# connect_4_v4.net
KiCad netlist of a schematic drawn in EasyEDA
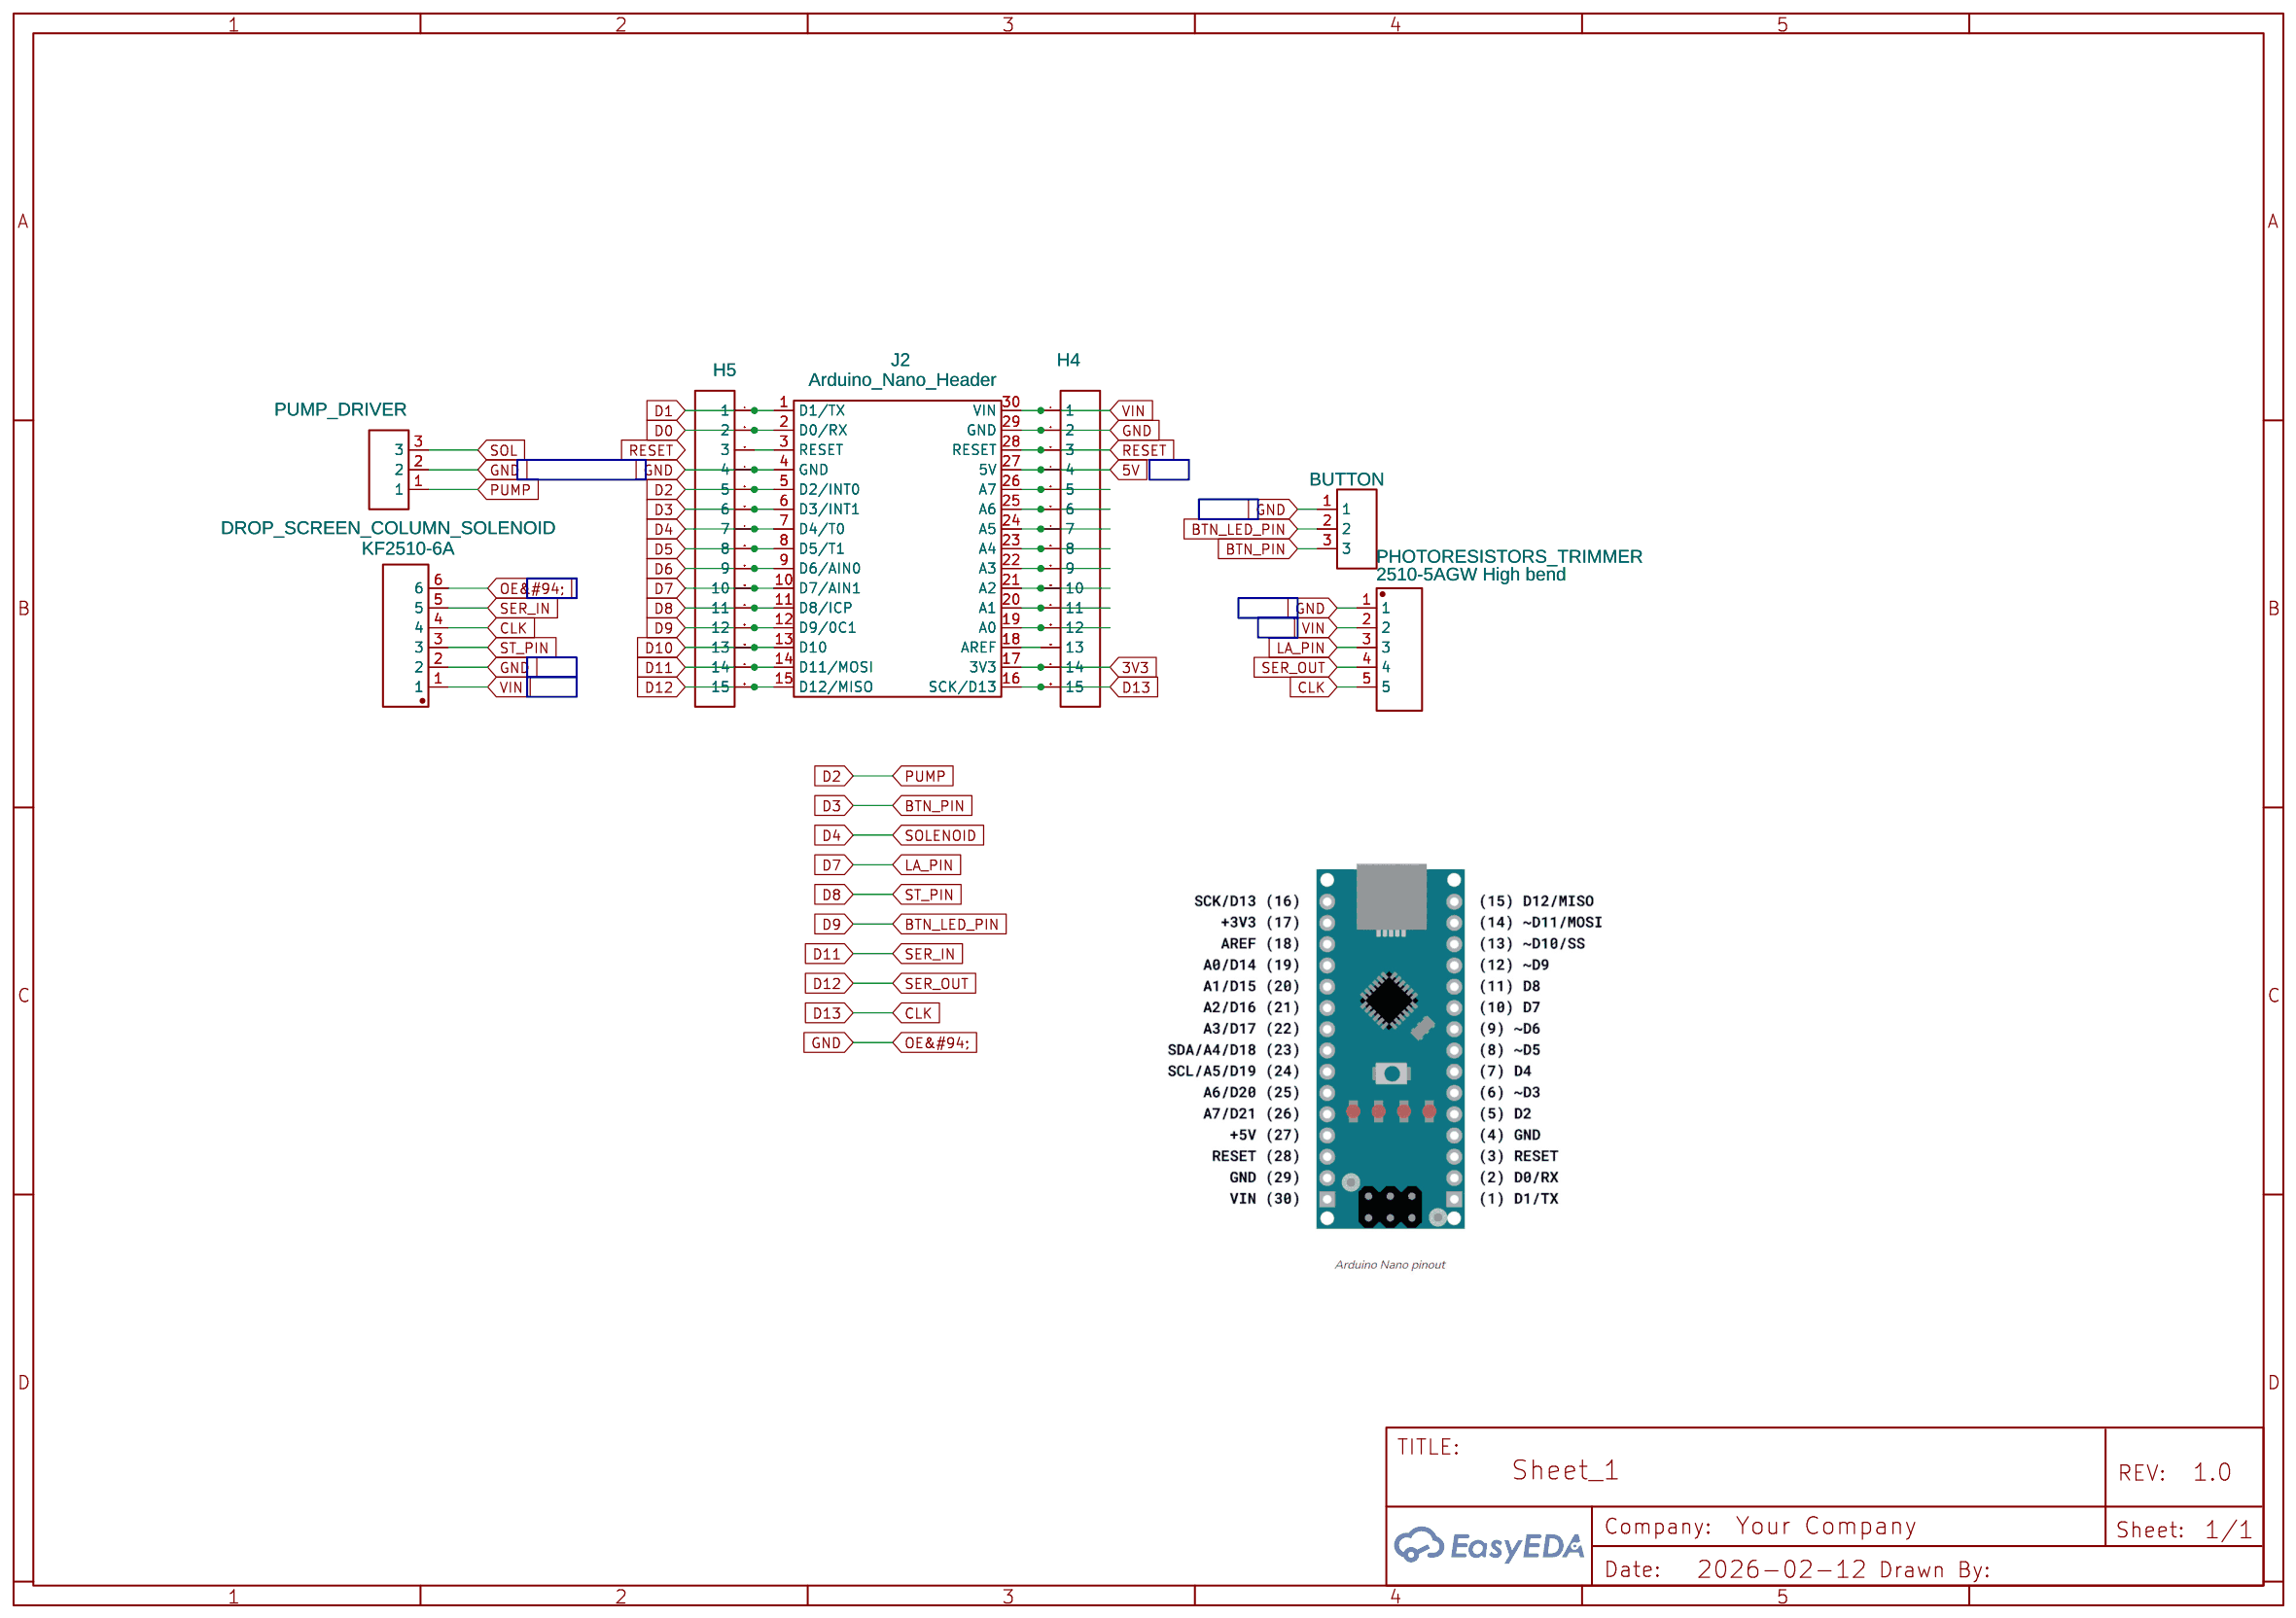
[diagram p0: schematic sheet]

(export (version "E")
  (design (tool "Eeschema 10.0.6"))
  (components
    (comp (ref "BUTTON") (value "FK2510") (libsource (lib "") (part "kf2510_3A_1")))
    (comp (ref "DROP_SCREEN_COLUMN_SOLENOID")
      (value "KF2510-6A")
      (fields (field (name "Manufacturer Part") "KF2510-6A针座"))
      (libsource (lib "") (part "KF2510-6A"))
    )
    (comp (ref "H4") (value "HDR-F-2.54_1x15") (libsource (lib "") (part "HDR-F-2.54_1x15")))
    (comp (ref "H5") (value "HDR-F-2.54_1x15") (libsource (lib "") (part "HDR-F-2.54_1x15_1")))
    (comp (ref "J2") (value "Arduino_Nano_Header") (libsource (lib "") (part "Arduino_Nano_Header")))
    (comp (ref "PHOTORESISTORS_TRIMMER")
      (value "2510-5AGW High bend")
      (fields (field (name "Manufacturer Part") "2510-5A高弯") (field (name "Manufacturer") "BOOMELE(博穆精密)"))
      (libsource (lib "") (part "2510-5AGW High bend"))
    )
    (comp (ref "PUMP_DRIVER") (value "FK2510") (libsource (lib "") (part "kf2510_3A")))
  )
  (nets
    (net (code "1") (name "3V3") (class "Default")
      (node (ref "H4") (pin "14") (pinfunction "14_14") (pintype "unspecified"))
      (node (ref "J2") (pin "17") (pinfunction "3V3_17") (pintype "unspecified"))
    )
    (net (code "2") (name "5V") (class "Default")
      (node (ref "H4") (pin "4") (pinfunction "4_4") (pintype "unspecified"))
      (node (ref "J2") (pin "27") (pinfunction "5V_27") (pintype "unspecified"))
    )
    (net (code "3") (name "BTN_LED_PIN") (class "Default")
      (node (ref "BUTTON") (pin "2") (pinfunction "2_2") (pintype "unspecified"))
      (node (ref "H5") (pin "12") (pinfunction "12_12") (pintype "unspecified"))
      (node (ref "J2") (pin "12") (pinfunction "D9/0C1_12") (pintype "unspecified"))
    )
    (net (code "4") (name "BTN_PIN") (class "Default")
      (node (ref "BUTTON") (pin "3") (pinfunction "3_3") (pintype "unspecified"))
      (node (ref "H5") (pin "6") (pinfunction "6_6") (pintype "unspecified"))
      (node (ref "J2") (pin "6") (pinfunction "D3/INT1_6") (pintype "unspecified"))
    )
    (net (code "5") (name "CLK") (class "Default")
      (node (ref "DROP_SCREEN_COLUMN_SOLENOID") (pin "4") (pinfunction "4_4") (pintype "unspecified"))
      (node (ref "H4") (pin "15") (pinfunction "15_15") (pintype "unspecified"))
      (node (ref "J2") (pin "16") (pinfunction "SCK/D13_16") (pintype "unspecified"))
      (node (ref "PHOTORESISTORS_TRIMMER") (pin "5") (pinfunction "5_5") (pintype "unspecified"))
    )
    (net (code "6") (name "D0") (class "Default")
      (node (ref "H5") (pin "2") (pinfunction "2_2") (pintype "unspecified"))
      (node (ref "J2") (pin "2") (pinfunction "D0/RX_2") (pintype "unspecified"))
    )
    (net (code "7") (name "D1") (class "Default")
      (node (ref "H5") (pin "1") (pinfunction "1_1") (pintype "unspecified"))
      (node (ref "J2") (pin "1") (pinfunction "D1/TX_1") (pintype "unspecified"))
    )
    (net (code "8") (name "D2") (class "Default")
      (node (ref "H5") (pin "5") (pinfunction "5_5") (pintype "unspecified"))
      (node (ref "J2") (pin "5") (pinfunction "D2/INT0_5") (pintype "unspecified"))
      (node (ref "PUMP_DRIVER") (pin "1") (pinfunction "1_1") (pintype "unspecified"))
    )
    (net (code "9") (name "D4") (class "Default")
      (node (ref "H5") (pin "7") (pinfunction "7_7") (pintype "unspecified"))
      (node (ref "J2") (pin "7") (pinfunction "D4/T0_7") (pintype "unspecified"))
    )
    (net (code "10") (name "D5") (class "Default")
      (node (ref "H5") (pin "8") (pinfunction "8_8") (pintype "unspecified"))
      (node (ref "J2") (pin "8") (pinfunction "D5/T1_8") (pintype "unspecified"))
    )
    (net (code "11") (name "D6") (class "Default")
      (node (ref "H5") (pin "9") (pinfunction "9_9") (pintype "unspecified"))
      (node (ref "J2") (pin "9") (pinfunction "D6/AIN0_9") (pintype "unspecified"))
    )
    (net (code "12") (name "D7") (class "Default")
      (node (ref "H5") (pin "10") (pinfunction "10_10") (pintype "unspecified"))
      (node (ref "J2") (pin "10") (pinfunction "D7/AIN1_10") (pintype "unspecified"))
      (node (ref "PHOTORESISTORS_TRIMMER") (pin "3") (pinfunction "3_3") (pintype "unspecified"))
    )
    (net (code "13") (name "D8") (class "Default")
      (node (ref "DROP_SCREEN_COLUMN_SOLENOID") (pin "3") (pinfunction "3_3") (pintype "unspecified"))
      (node (ref "H5") (pin "11") (pinfunction "11_11") (pintype "unspecified"))
      (node (ref "J2") (pin "11") (pinfunction "D8/ICP_11") (pintype "unspecified"))
    )
    (net (code "14") (name "D10") (class "Default")
      (node (ref "H5") (pin "13") (pinfunction "13_13") (pintype "unspecified"))
      (node (ref "J2") (pin "13") (pinfunction "D10_13") (pintype "unspecified"))
    )
    (net (code "15") (name "D11") (class "Default")
      (node (ref "DROP_SCREEN_COLUMN_SOLENOID") (pin "5") (pinfunction "5_5") (pintype "unspecified"))
      (node (ref "H5") (pin "14") (pinfunction "14_14") (pintype "unspecified"))
      (node (ref "J2") (pin "14") (pinfunction "D11/MOSI_14") (pintype "unspecified"))
    )
    (net (code "16") (name "D12") (class "Default")
      (node (ref "H5") (pin "15") (pinfunction "15_15") (pintype "unspecified"))
      (node (ref "J2") (pin "15") (pinfunction "D12/MISO_15") (pintype "unspecified"))
      (node (ref "PHOTORESISTORS_TRIMMER") (pin "4") (pinfunction "4_4") (pintype "unspecified"))
    )
    (net (code "17") (name "GND") (class "Default")
      (node (ref "BUTTON") (pin "1") (pinfunction "1_1") (pintype "unspecified"))
      (node (ref "DROP_SCREEN_COLUMN_SOLENOID") (pin "2") (pinfunction "2_2") (pintype "unspecified"))
      (node (ref "DROP_SCREEN_COLUMN_SOLENOID") (pin "6") (pinfunction "6_6") (pintype "unspecified"))
      (node (ref "H4") (pin "2") (pinfunction "2_2") (pintype "unspecified"))
      (node (ref "H5") (pin "4") (pinfunction "4_4") (pintype "unspecified"))
      (node (ref "J2") (pin "29") (pinfunction "GND_29") (pintype "unspecified"))
      (node (ref "J2") (pin "4") (pinfunction "GND_4") (pintype "unspecified"))
      (node (ref "PHOTORESISTORS_TRIMMER") (pin "1") (pinfunction "1_1") (pintype "unspecified"))
      (node (ref "PUMP_DRIVER") (pin "2") (pinfunction "2_2") (pintype "unspecified"))
    )
    (net (code "18") (name "Net-(H5-Pad3)") (class "Default")
      (node (ref "H5") (pin "3") (pinfunction "3_3") (pintype "unspecified"))
      (node (ref "J2") (pin "3") (pinfunction "RESET_3") (pintype "unspecified"))
    )
    (net (code "19") (name "Net-(J2-A0)") (class "Default")
      (node (ref "H4") (pin "12") (pinfunction "12_12") (pintype "unspecified"))
      (node (ref "J2") (pin "19") (pinfunction "A0_19") (pintype "unspecified"))
    )
    (net (code "20") (name "Net-(J2-A1)") (class "Default")
      (node (ref "H4") (pin "11") (pinfunction "11_11") (pintype "unspecified"))
      (node (ref "J2") (pin "20") (pinfunction "A1_20") (pintype "unspecified"))
    )
    (net (code "21") (name "Net-(J2-A2)") (class "Default")
      (node (ref "H4") (pin "10") (pinfunction "10_10") (pintype "unspecified"))
      (node (ref "J2") (pin "21") (pinfunction "A2_21") (pintype "unspecified"))
    )
    (net (code "22") (name "Net-(J2-A3)") (class "Default")
      (node (ref "H4") (pin "9") (pinfunction "9_9") (pintype "unspecified"))
      (node (ref "J2") (pin "22") (pinfunction "A3_22") (pintype "unspecified"))
    )
    (net (code "23") (name "Net-(J2-A4)") (class "Default")
      (node (ref "H4") (pin "8") (pinfunction "8_8") (pintype "unspecified"))
      (node (ref "J2") (pin "23") (pinfunction "A4_23") (pintype "unspecified"))
    )
    (net (code "24") (name "Net-(J2-A5)") (class "Default")
      (node (ref "H4") (pin "7") (pinfunction "7_7") (pintype "unspecified"))
      (node (ref "J2") (pin "24") (pinfunction "A5_24") (pintype "unspecified"))
    )
    (net (code "25") (name "Net-(J2-A6)") (class "Default")
      (node (ref "H4") (pin "6") (pinfunction "6_6") (pintype "unspecified"))
      (node (ref "J2") (pin "25") (pinfunction "A6_25") (pintype "unspecified"))
    )
    (net (code "26") (name "Net-(J2-A7)") (class "Default")
      (node (ref "H4") (pin "5") (pinfunction "5_5") (pintype "unspecified"))
      (node (ref "J2") (pin "26") (pinfunction "A7_26") (pintype "unspecified"))
    )
    (net (code "27") (name "Net-(J2-AREF)") (class "Default")
      (node (ref "H4") (pin "13") (pinfunction "13_13") (pintype "unspecified"))
      (node (ref "J2") (pin "18") (pinfunction "AREF_18") (pintype "unspecified"))
    )
    (net (code "28") (name "RESET") (class "Default")
      (node (ref "H4") (pin "3") (pinfunction "3_3") (pintype "unspecified"))
      (node (ref "J2") (pin "28") (pinfunction "RESET_28") (pintype "unspecified"))
    )
    (net (code "29") (name "SOL") (class "Default")
      (node (ref "PUMP_DRIVER") (pin "3") (pinfunction "3_3") (pintype "unspecified"))
    )
    (net (code "30") (name "VIN") (class "Default")
      (node (ref "DROP_SCREEN_COLUMN_SOLENOID") (pin "1") (pinfunction "1_1") (pintype "unspecified"))
      (node (ref "H4") (pin "1") (pinfunction "1_1") (pintype "unspecified"))
      (node (ref "J2") (pin "30") (pinfunction "VIN_30") (pintype "unspecified"))
      (node (ref "PHOTORESISTORS_TRIMMER") (pin "2") (pinfunction "2_2") (pintype "unspecified"))
    )
  )
)
